# Power_Isolation.net
KiCad netlist of a schematic drawn in Altium Designer
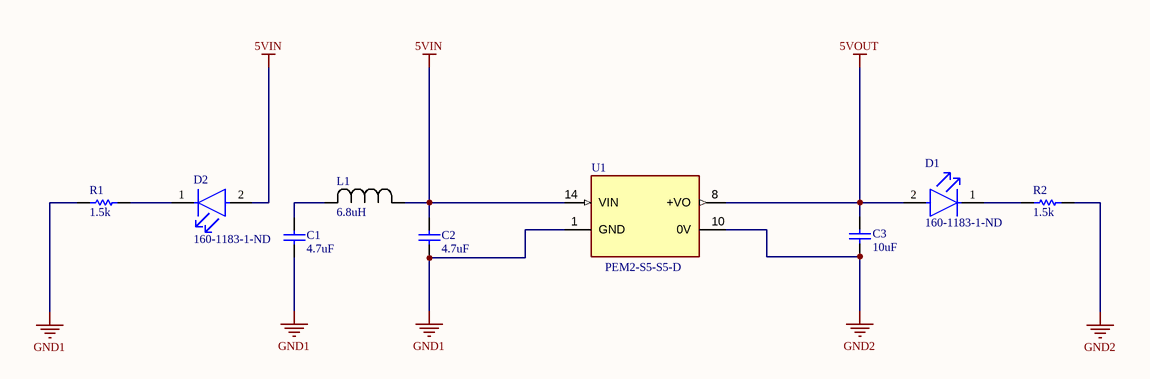
[diagram p0: Power Isolation.SchDoc]

(export (version "E")
  (design (tool "Eeschema 10.0.6"))
  (components
    (comp (ref "C1")
      (value "4.7uF")
      (footprint "1206C")
      (description "CAP CER 4.7UF 50V X7R 1206")
      (fields
        (field (name "MANUFACTURER") "Murata")
        (field (name "MANUFACTURER PART NUMBER") "GRM31CR71H475KA12L")
      )
      (libsource (lib "USB_isolator") (part "GRM31CR71H475KA12L"))
    )
    (comp (ref "C2")
      (value "4.7uF")
      (footprint "1206C")
      (description "CAP CER 4.7UF 50V X7R 1206")
      (fields
        (field (name "MANUFACTURER") "Murata")
        (field (name "MANUFACTURER PART NUMBER") "GRM31CR71H475KA12L")
      )
      (libsource (lib "USB_isolator") (part "GRM31CR71H475KA12L"))
    )
    (comp (ref "C3")
      (value "10uF")
      (footprint "1206C")
      (description "Capacitor 10uF ±20% 25V 1206")
      (fields
        (field (name "MANUFACTURER") "Taiyo Yuden")
        (field (name "MANUFACTURER PART NUMBER") "TMK316BJ106ML-T")
      )
      (libsource (lib "USB_isolator") (part "TMK316BJ106ML-T"))
    )
    (comp (ref "D1")
      (value "LED")
      (footprint "Lite-On_0_MFG")
      (description "LED 0603(H=0.9mm) λD=569nm VR=5V VF=2.1V~2.6V IF=20mA PD=100mW")
      (fields
        (field (name "MANUFACTURER") "Vishay Lite-On")
        (field (name "MANUFACTURER PART NUMBER") "LTST-C190GKT")
        (field (name "SUPPLIER PART NUMBER 1") "160-1183-1-ND")
      )
      (libsource (lib "USB_isolator") (part "LTST-C190GKT"))
    )
    (comp (ref "D2")
      (value "LED")
      (footprint "Lite-On_0_MFG")
      (description "LED 0603(H=0.9mm) λD=569nm VR=5V VF=2.1V~2.6V IF=20mA PD=100mW")
      (fields
        (field (name "MANUFACTURER") "Vishay Lite-On")
        (field (name "MANUFACTURER PART NUMBER") "LTST-C190GKT")
        (field (name "SUPPLIER PART NUMBER 1") "160-1183-1-ND")
      )
      (libsource (lib "USB_isolator") (part "LTST-C190GKT"))
    )
    (comp (ref "L1")
      (value "6.8uH")
      (footprint "IND_TAIYO_LBC3225_TAY")
      (description "Inductor General Purpose Chip Wirewound 6.8uH 20% 100KHz Ferrite 0.62A 0.156Ohm DCR 1210 T/R")
      (fields
        (field (name "MANUFACTURER_PART_NUMBER") "LBC3225T6R8MR")
        (field (name "MANUFACTURER") "Taiyo Yuden")
        (field (name "COPYRIGHT") "Copyright (C) 2022 Ultra Librarian. All rights reserved.")
      )
      (libsource (lib "USB_isolator") (part "LBC3225T6R8MR_1"))
    )
    (comp (ref "R1")
      (value "1.5k")
      (footprint "0805R")
      (description "Res Thick Film 0805 1.5K Ohm 1% 1/8W ±100ppm/°C Molded SMD Paper T/R")
      (fields
        (field (name "MANUFACTURER") "Vishay")
        (field (name "MANUFACTURER PART NUMBER") "CRCW08051K50FKEA")
      )
      (libsource (lib "USB_isolator") (part "CRCW08051K50FKEA"))
    )
    (comp (ref "R2")
      (value "1.5k")
      (footprint "0805R")
      (description "Res Thick Film 0805 1.5K Ohm 1% 1/8W ±100ppm/°C Molded SMD Paper T/R")
      (fields
        (field (name "MANUFACTURER") "Vishay")
        (field (name "MANUFACTURER PART NUMBER") "CRCW08051K50FKEA")
      )
      (libsource (lib "USB_isolator") (part "CRCW08051K50FKEA"))
    )
    (comp (ref "U1")
      (value "PEM2-S5-S5-D")
      (footprint "CONV_PEM2-S5-S5-D")
      (description "2 W, 5 V, 400 mA, Single Unregulated Output, Isolated Dc-Dc converter")
      (fields (field (name "MANUFACTURER") "CUI") (field (name "MP") "PEM2-S5-S5-D"))
      (libsource (lib "USB_isolator") (part "PEM2-S5-S5-D"))
    )
  )
  (nets
    (net (code "1") (name "5VIN") (class "Default")
      (node (ref "C2") (pin "2") (pinfunction "2_2") (pintype "passive"))
      (node (ref "D2") (pin "2") (pinfunction "A_2") (pintype "passive"))
      (node (ref "L1") (pin "1") (pinfunction "1_1") (pintype "passive"))
      (node (ref "U1") (pin "14") (pinfunction "VIN_14") (pintype "input"))
    )
    (net (code "2") (name "5VOUT") (class "Default")
      (node (ref "C3") (pin "2") (pinfunction "2_2") (pintype "passive"))
      (node (ref "D1") (pin "2") (pinfunction "A_2") (pintype "passive"))
      (node (ref "U1") (pin "8") (pinfunction "+VO_8") (pintype "output"))
    )
    (net (code "3") (name "GND1") (class "Default")
      (node (ref "C1") (pin "1") (pinfunction "1_1") (pintype "passive"))
      (node (ref "C2") (pin "1") (pinfunction "1_1") (pintype "passive"))
      (node (ref "R1") (pin "1") (pinfunction "1_1") (pintype "passive"))
      (node (ref "U1") (pin "1") (pinfunction "GND_1") (pintype "power_in"))
    )
    (net (code "4") (name "GND2") (class "Default")
      (node (ref "C3") (pin "1") (pinfunction "1_1") (pintype "passive"))
      (node (ref "R2") (pin "2") (pinfunction "2_2") (pintype "passive"))
      (node (ref "U1") (pin "10") (pinfunction "0V_10") (pintype "power_in"))
    )
    (net (code "5") (name "Net-(C1-Pad2)") (class "Default")
      (node (ref "C1") (pin "2") (pinfunction "2_2") (pintype "passive"))
      (node (ref "L1") (pin "2") (pinfunction "2_2") (pintype "passive"))
    )
    (net (code "6") (name "Net-(D1-C)") (class "Default")
      (node (ref "D1") (pin "1") (pinfunction "C_1") (pintype "passive"))
      (node (ref "R2") (pin "1") (pinfunction "1_1") (pintype "passive"))
    )
    (net (code "7") (name "Net-(D2-C)") (class "Default")
      (node (ref "D2") (pin "1") (pinfunction "C_1") (pintype "passive"))
      (node (ref "R1") (pin "2") (pinfunction "2_2") (pintype "passive"))
    )
  )
)
